# S4CX11.net
KiCad netlist of a schematic drawn in EAGLE
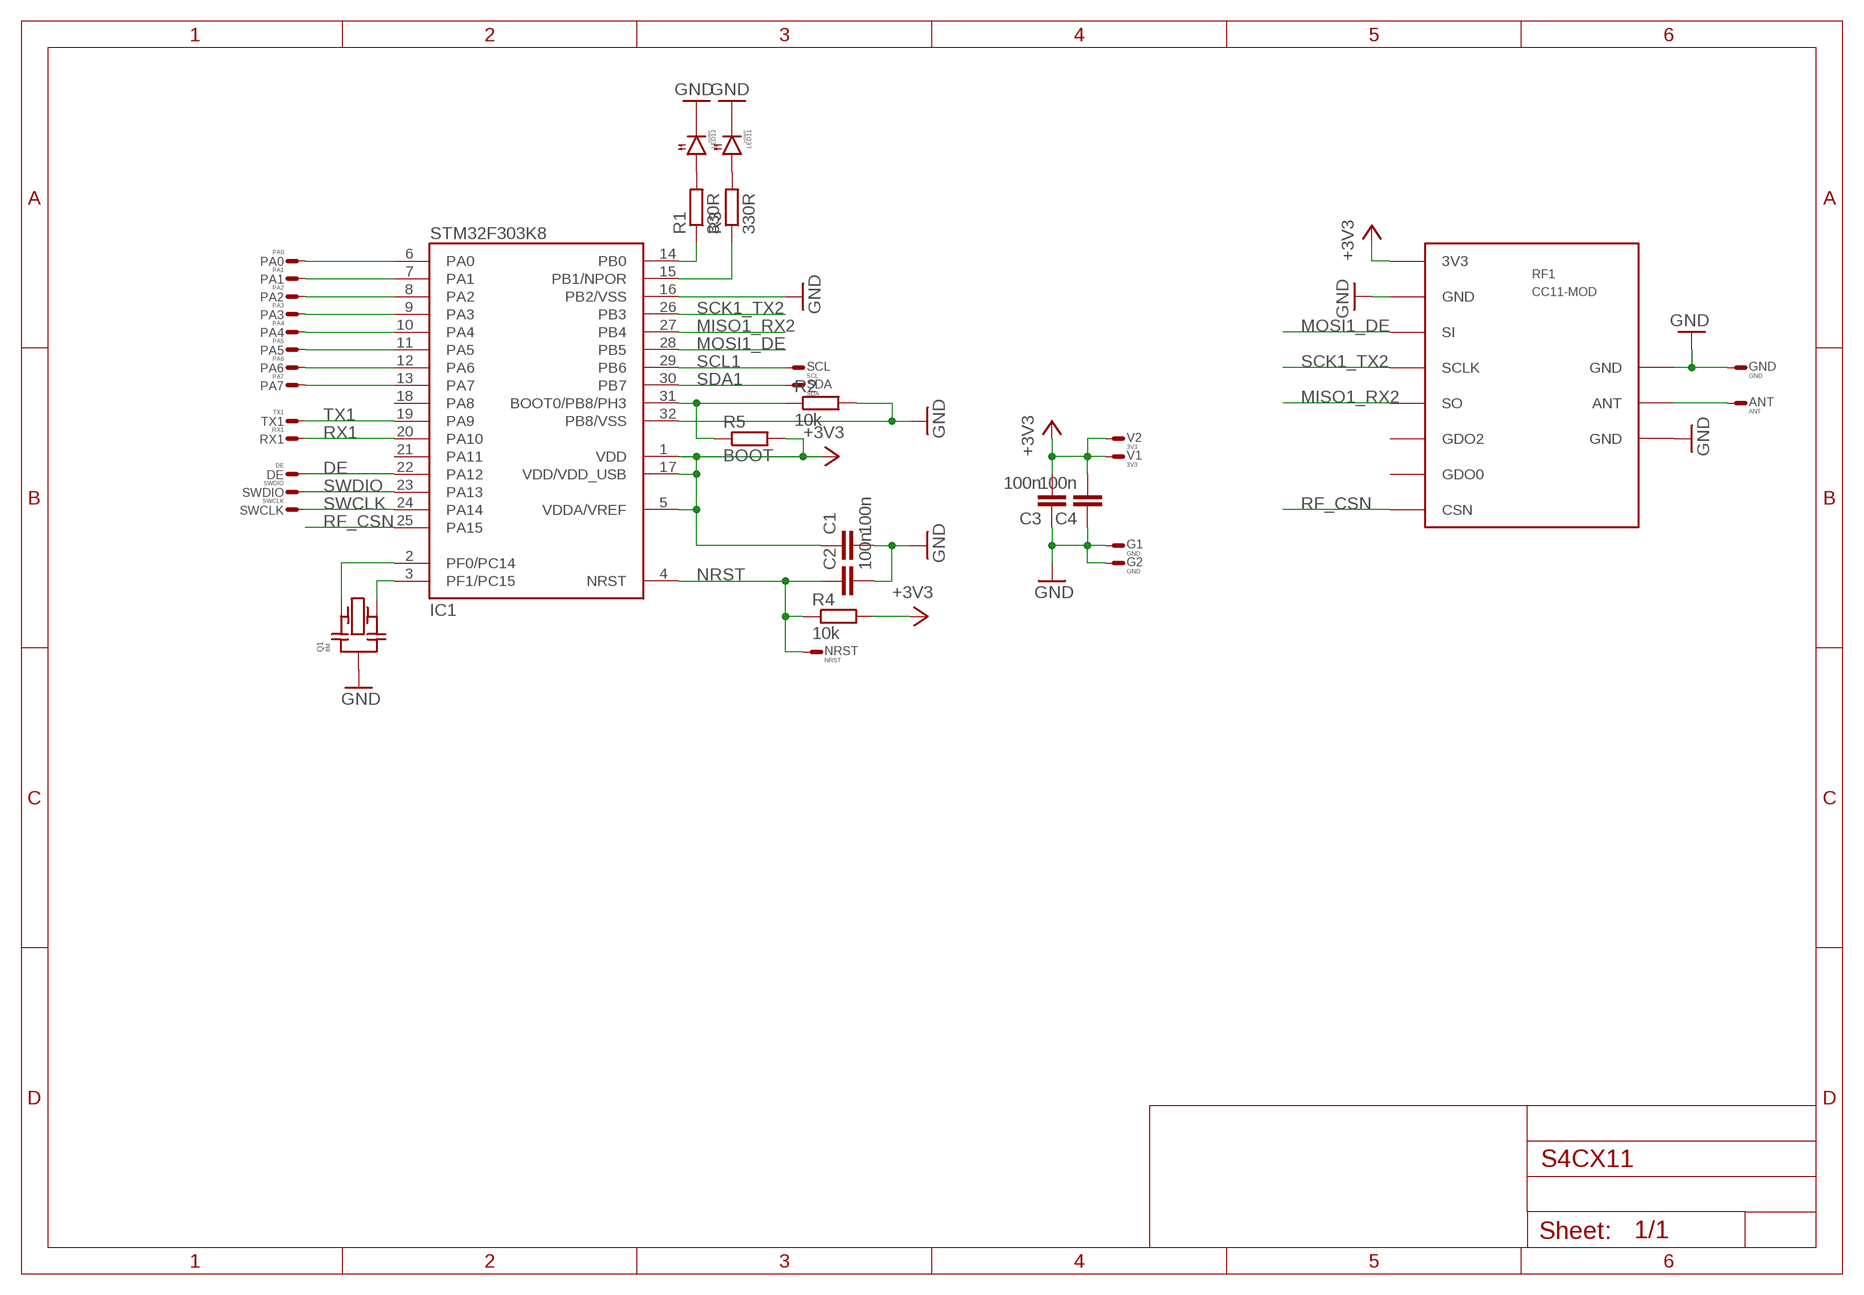
[diagram p0: schematic, sheet 1]

(export (version "E")
  (design (tool "Eeschema 10.0.6"))
  (components
    (comp (ref "ANT")
      (value "ANT")
      (footprint "eagle-import:T1.6_0.9")
      (libsource (lib "eagle-import") (part "WIREPADT1.6/0.9"))
    )
    (comp (ref "C1")
      (value "100n")
      (footprint "eagle-import:0603")
      (libsource (lib "eagle-import") (part "C0603"))
    )
    (comp (ref "C2")
      (value "100n")
      (footprint "eagle-import:0603")
      (libsource (lib "eagle-import") (part "C0603"))
    )
    (comp (ref "C3")
      (value "100n")
      (footprint "eagle-import:0603")
      (libsource (lib "eagle-import") (part "C0603"))
    )
    (comp (ref "C4")
      (value "100n")
      (footprint "eagle-import:0603")
      (libsource (lib "eagle-import") (part "C0603"))
    )
    (comp (ref "DE")
      (value "DE")
      (footprint "eagle-import:T1.6_0.9")
      (libsource (lib "eagle-import") (part "WIREPADT1.6/0.9"))
    )
    (comp (ref "G1")
      (value "GND")
      (footprint "eagle-import:T1.6_0.9")
      (libsource (lib "eagle-import") (part "WIREPADT1.6/0.9"))
    )
    (comp (ref "G2")
      (value "GND")
      (footprint "eagle-import:T1.6_0.9")
      (libsource (lib "eagle-import") (part "WIREPADT1.6/0.9"))
    )
    (comp (ref "GND")
      (value "GND")
      (footprint "eagle-import:T1.6_0.9")
      (libsource (lib "eagle-import") (part "WIREPADT1.6/0.9"))
    )
    (comp (ref "IC1")
      (value "STM32F303K8")
      (footprint "eagle-import:LQFP32-7X7")
      (libsource (lib "eagle-import") (part "STM32_LQFP32"))
    )
    (comp (ref "LED1")
      (value "HSMF")
      (footprint "eagle-import:HSMF")
      (libsource (lib "eagle-import") (part "2LEDH"))
    )
    (comp (ref "NRST")
      (value "NRST")
      (footprint "eagle-import:T1.6_0.9")
      (libsource (lib "eagle-import") (part "WIREPADT1.6/0.9"))
    )
    (comp (ref "PA0")
      (value "PA0")
      (footprint "eagle-import:T1.6_0.9")
      (libsource (lib "eagle-import") (part "WIREPADT1.6/0.9"))
    )
    (comp (ref "PA1")
      (value "PA1")
      (footprint "eagle-import:T1.6_0.9")
      (libsource (lib "eagle-import") (part "WIREPADT1.6/0.9"))
    )
    (comp (ref "PA2")
      (value "PA2")
      (footprint "eagle-import:T1.6_0.9")
      (libsource (lib "eagle-import") (part "WIREPADT1.6/0.9"))
    )
    (comp (ref "PA3")
      (value "PA3")
      (footprint "eagle-import:T1.6_0.9")
      (libsource (lib "eagle-import") (part "WIREPADT1.6/0.9"))
    )
    (comp (ref "PA4")
      (value "PA4")
      (footprint "eagle-import:T1.6_0.9")
      (libsource (lib "eagle-import") (part "WIREPADT1.6/0.9"))
    )
    (comp (ref "PA5")
      (value "PA5")
      (footprint "eagle-import:T1.6_0.9")
      (libsource (lib "eagle-import") (part "WIREPADT1.6/0.9"))
    )
    (comp (ref "PA6")
      (value "PA6")
      (footprint "eagle-import:T1.6_0.9")
      (libsource (lib "eagle-import") (part "WIREPADT1.6/0.9"))
    )
    (comp (ref "PA7")
      (value "PA7")
      (footprint "eagle-import:T1.6_0.9")
      (libsource (lib "eagle-import") (part "WIREPADT1.6/0.9"))
    )
    (comp (ref "Q1")
      (value "8M")
      (footprint "eagle-import:CSTCE")
      (libsource (lib "eagle-import") (part "QRCE"))
    )
    (comp (ref "R1")
      (value "330R")
      (footprint "eagle-import:0603")
      (libsource (lib "eagle-import") (part "R0603"))
    )
    (comp (ref "R2")
      (value "10k")
      (footprint "eagle-import:0603")
      (libsource (lib "eagle-import") (part "R0603"))
    )
    (comp (ref "R3")
      (value "330R")
      (footprint "eagle-import:0603")
      (libsource (lib "eagle-import") (part "R0603"))
    )
    (comp (ref "R4")
      (value "10k")
      (footprint "eagle-import:0603")
      (libsource (lib "eagle-import") (part "R0603"))
    )
    (comp (ref "R5")
      (value "BOOT")
      (footprint "eagle-import:1206")
      (libsource (lib "eagle-import") (part "R1206"))
    )
    (comp (ref "RF1")
      (value "CC11-MOD")
      (footprint "eagle-import:CC11-MOD")
      (libsource (lib "eagle-import") (part "CC11-MOD"))
    )
    (comp (ref "RX1")
      (value "RX1")
      (footprint "eagle-import:T1.6_0.9")
      (libsource (lib "eagle-import") (part "WIREPADT1.6/0.9"))
    )
    (comp (ref "SCL")
      (value "SCL")
      (footprint "eagle-import:T1.6_0.9")
      (libsource (lib "eagle-import") (part "WIREPADT1.6/0.9"))
    )
    (comp (ref "SDA")
      (value "SDA")
      (footprint "eagle-import:T1.6_0.9")
      (libsource (lib "eagle-import") (part "WIREPADT1.6/0.9"))
    )
    (comp (ref "SWCLK")
      (value "SWCLK")
      (footprint "eagle-import:T1.6_0.9")
      (libsource (lib "eagle-import") (part "WIREPADT1.6/0.9"))
    )
    (comp (ref "SWDIO")
      (value "SWDIO")
      (footprint "eagle-import:T1.6_0.9")
      (libsource (lib "eagle-import") (part "WIREPADT1.6/0.9"))
    )
    (comp (ref "TX1")
      (value "TX1")
      (footprint "eagle-import:T1.6_0.9")
      (libsource (lib "eagle-import") (part "WIREPADT1.6/0.9"))
    )
    (comp (ref "V1")
      (value "3V3")
      (footprint "eagle-import:T1.6_0.9")
      (libsource (lib "eagle-import") (part "WIREPADT1.6/0.9"))
    )
    (comp (ref "V2")
      (value "3V3")
      (footprint "eagle-import:T1.6_0.9")
      (libsource (lib "eagle-import") (part "WIREPADT1.6/0.9"))
    )
  )
  (nets
    (net (code "1") (name "+3V3") (class "Default")
      (node (ref "C1") (pin "1") (pinfunction "1_1") (pintype "passive"))
      (node (ref "C3") (pin "2") (pinfunction "2_2") (pintype "passive"))
      (node (ref "C4") (pin "2") (pinfunction "2_2") (pintype "passive"))
      (node (ref "IC1") (pin "1") (pinfunction "VDD_1") (pintype "bidirectional"))
      (node (ref "IC1") (pin "17") (pinfunction "VDD/VDD_USB_17") (pintype "bidirectional"))
      (node (ref "IC1") (pin "5") (pinfunction "VDDA/VREF_5") (pintype "bidirectional"))
      (node (ref "R4") (pin "2") (pinfunction "2_2") (pintype "passive"))
      (node (ref "R5") (pin "2") (pinfunction "2_2") (pintype "passive"))
      (node (ref "RF1") (pin "3V3") (pinfunction "3V3_3V3") (pintype "bidirectional"))
      (node (ref "V1") (pin "1") (pinfunction "S_1") (pintype "passive"))
      (node (ref "V2") (pin "1") (pinfunction "S_1") (pintype "passive"))
    )
    (net (code "2") (name "/DE") (class "Default")
      (node (ref "DE") (pin "1") (pinfunction "S_1") (pintype "passive"))
      (node (ref "IC1") (pin "22") (pinfunction "PA12_22") (pintype "bidirectional"))
    )
    (net (code "3") (name "/MISO1_RX2") (class "Default")
      (node (ref "IC1") (pin "27") (pinfunction "PB4_27") (pintype "bidirectional"))
      (node (ref "RF1") (pin "SO") (pinfunction "SO_SO") (pintype "bidirectional"))
    )
    (net (code "4") (name "/MOSI1_DE") (class "Default")
      (node (ref "IC1") (pin "28") (pinfunction "PB5_28") (pintype "bidirectional"))
      (node (ref "RF1") (pin "SI") (pinfunction "SI_SI") (pintype "bidirectional"))
    )
    (net (code "5") (name "/NRST") (class "Default")
      (node (ref "C2") (pin "1") (pinfunction "1_1") (pintype "passive"))
      (node (ref "IC1") (pin "4") (pinfunction "NRST_4") (pintype "bidirectional"))
      (node (ref "NRST") (pin "1") (pinfunction "S_1") (pintype "passive"))
      (node (ref "R4") (pin "1") (pinfunction "1_1") (pintype "passive"))
    )
    (net (code "6") (name "/RF_CSN") (class "Default")
      (node (ref "IC1") (pin "25") (pinfunction "PA15_25") (pintype "bidirectional"))
      (node (ref "RF1") (pin "CSN") (pinfunction "CSN_CSN") (pintype "bidirectional"))
    )
    (net (code "7") (name "/RX1") (class "Default")
      (node (ref "IC1") (pin "20") (pinfunction "PA10_20") (pintype "bidirectional"))
      (node (ref "RX1") (pin "1") (pinfunction "S_1") (pintype "passive"))
    )
    (net (code "8") (name "/SCK1_TX2") (class "Default")
      (node (ref "IC1") (pin "26") (pinfunction "PB3_26") (pintype "bidirectional"))
      (node (ref "RF1") (pin "SCLK") (pinfunction "SCLK_SCLK") (pintype "bidirectional"))
    )
    (net (code "9") (name "/SCL1") (class "Default")
      (node (ref "IC1") (pin "29") (pinfunction "PB6_29") (pintype "bidirectional"))
      (node (ref "SCL") (pin "1") (pinfunction "S_1") (pintype "passive"))
    )
    (net (code "10") (name "/SDA1") (class "Default")
      (node (ref "IC1") (pin "30") (pinfunction "PB7_30") (pintype "bidirectional"))
      (node (ref "SDA") (pin "1") (pinfunction "S_1") (pintype "passive"))
    )
    (net (code "11") (name "/SWCLK") (class "Default")
      (node (ref "IC1") (pin "24") (pinfunction "PA14_24") (pintype "bidirectional"))
      (node (ref "SWCLK") (pin "1") (pinfunction "S_1") (pintype "passive"))
    )
    (net (code "12") (name "/SWDIO") (class "Default")
      (node (ref "IC1") (pin "23") (pinfunction "PA13_23") (pintype "bidirectional"))
      (node (ref "SWDIO") (pin "1") (pinfunction "S_1") (pintype "passive"))
    )
    (net (code "13") (name "/TX1") (class "Default")
      (node (ref "IC1") (pin "19") (pinfunction "PA9_19") (pintype "bidirectional"))
      (node (ref "TX1") (pin "1") (pinfunction "S_1") (pintype "passive"))
    )
    (net (code "14") (name "GND") (class "Default")
      (node (ref "C1") (pin "2") (pinfunction "2_2") (pintype "passive"))
      (node (ref "C2") (pin "2") (pinfunction "2_2") (pintype "passive"))
      (node (ref "C3") (pin "1") (pinfunction "1_1") (pintype "passive"))
      (node (ref "C4") (pin "1") (pinfunction "1_1") (pintype "passive"))
      (node (ref "G1") (pin "1") (pinfunction "S_1") (pintype "passive"))
      (node (ref "G2") (pin "1") (pinfunction "S_1") (pintype "passive"))
      (node (ref "GND") (pin "1") (pinfunction "S_1") (pintype "passive"))
      (node (ref "IC1") (pin "16") (pinfunction "PB2/VSS_16") (pintype "bidirectional"))
      (node (ref "IC1") (pin "32") (pinfunction "PB8/VSS_32") (pintype "bidirectional"))
      (node (ref "LED1") (pin "2") (pinfunction "C_2") (pintype "bidirectional"))
      (node (ref "LED1") (pin "4") (pinfunction "C_4") (pintype "bidirectional"))
      (node (ref "Q1") (pin "G") (pinfunction "M_G") (pintype "passive"))
      (node (ref "R2") (pin "2") (pinfunction "2_2") (pintype "passive"))
      (node (ref "RF1") (pin "GND@1") (pinfunction "GND_GND@1") (pintype "bidirectional"))
      (node (ref "RF1") (pin "GND@2") (pinfunction "GND_GND@2") (pintype "bidirectional"))
      (node (ref "RF1") (pin "GND@3") (pinfunction "GND_GND@3") (pintype "bidirectional"))
    )
    (net (code "15") (name "Net-(ANT-S)") (class "Default")
      (node (ref "ANT") (pin "1") (pinfunction "S_1") (pintype "passive"))
      (node (ref "RF1") (pin "ANT") (pinfunction "ANT_ANT") (pintype "bidirectional"))
    )
    (net (code "16") (name "Net-(IC1-BOOT0{slash}PB8{slash}PH3)") (class "Default")
      (node (ref "IC1") (pin "31") (pinfunction "BOOT0/PB8/PH3_31") (pintype "bidirectional"))
      (node (ref "R2") (pin "1") (pinfunction "1_1") (pintype "passive"))
      (node (ref "R5") (pin "1") (pinfunction "1_1") (pintype "passive"))
    )
    (net (code "17") (name "Net-(IC1-PA0)") (class "Default")
      (node (ref "IC1") (pin "6") (pinfunction "PA0_6") (pintype "bidirectional"))
      (node (ref "PA0") (pin "1") (pinfunction "S_1") (pintype "passive"))
    )
    (net (code "18") (name "Net-(IC1-PA1)") (class "Default")
      (node (ref "IC1") (pin "7") (pinfunction "PA1_7") (pintype "bidirectional"))
      (node (ref "PA1") (pin "1") (pinfunction "S_1") (pintype "passive"))
    )
    (net (code "19") (name "Net-(IC1-PA2)") (class "Default")
      (node (ref "IC1") (pin "8") (pinfunction "PA2_8") (pintype "bidirectional"))
      (node (ref "PA2") (pin "1") (pinfunction "S_1") (pintype "passive"))
    )
    (net (code "20") (name "Net-(IC1-PA3)") (class "Default")
      (node (ref "IC1") (pin "9") (pinfunction "PA3_9") (pintype "bidirectional"))
      (node (ref "PA3") (pin "1") (pinfunction "S_1") (pintype "passive"))
    )
    (net (code "21") (name "Net-(IC1-PA4)") (class "Default")
      (node (ref "IC1") (pin "10") (pinfunction "PA4_10") (pintype "bidirectional"))
      (node (ref "PA4") (pin "1") (pinfunction "S_1") (pintype "passive"))
    )
    (net (code "22") (name "Net-(IC1-PA5)") (class "Default")
      (node (ref "IC1") (pin "11") (pinfunction "PA5_11") (pintype "bidirectional"))
      (node (ref "PA5") (pin "1") (pinfunction "S_1") (pintype "passive"))
    )
    (net (code "23") (name "Net-(IC1-PA6)") (class "Default")
      (node (ref "IC1") (pin "12") (pinfunction "PA6_12") (pintype "bidirectional"))
      (node (ref "PA6") (pin "1") (pinfunction "S_1") (pintype "passive"))
    )
    (net (code "24") (name "Net-(IC1-PA7)") (class "Default")
      (node (ref "IC1") (pin "13") (pinfunction "PA7_13") (pintype "bidirectional"))
      (node (ref "PA7") (pin "1") (pinfunction "S_1") (pintype "passive"))
    )
    (net (code "25") (name "Net-(IC1-PB0)") (class "Default")
      (node (ref "IC1") (pin "14") (pinfunction "PB0_14") (pintype "bidirectional"))
      (node (ref "R1") (pin "1") (pinfunction "1_1") (pintype "passive"))
    )
    (net (code "26") (name "Net-(IC1-PB1{slash}NPOR)") (class "Default")
      (node (ref "IC1") (pin "15") (pinfunction "PB1/NPOR_15") (pintype "bidirectional"))
      (node (ref "R3") (pin "1") (pinfunction "1_1") (pintype "passive"))
    )
    (net (code "27") (name "Net-(IC1-PF0{slash}PC14)") (class "Default")
      (node (ref "IC1") (pin "2") (pinfunction "PF0/PC14_2") (pintype "bidirectional"))
      (node (ref "Q1") (pin "A") (pinfunction "1_A") (pintype "passive"))
    )
    (net (code "28") (name "Net-(IC1-PF1{slash}PC15)") (class "Default")
      (node (ref "IC1") (pin "3") (pinfunction "PF1/PC15_3") (pintype "bidirectional"))
      (node (ref "Q1") (pin "B") (pinfunction "2_B") (pintype "passive"))
    )
    (net (code "29") (name "Net-(LED1A-A)") (class "Default")
      (node (ref "LED1") (pin "1") (pinfunction "A_1") (pintype "bidirectional"))
      (node (ref "R3") (pin "2") (pinfunction "2_2") (pintype "passive"))
    )
    (net (code "30") (name "Net-(LED1B-A)") (class "Default")
      (node (ref "LED1") (pin "3") (pinfunction "A_3") (pintype "bidirectional"))
      (node (ref "R1") (pin "2") (pinfunction "2_2") (pintype "passive"))
    )
    (net (code "31") (name "unconnected-(IC1-PA8-Pad18)") (class "Default")
      (node (ref "IC1") (pin "18") (pinfunction "PA8_18") (pintype "bidirectional"))
    )
    (net (code "32") (name "unconnected-(IC1-PA11-Pad21)") (class "Default")
      (node (ref "IC1") (pin "21") (pinfunction "PA11_21") (pintype "bidirectional"))
    )
    (net (code "33") (name "unconnected-(RF1-PadGDO0)") (class "Default")
      (node (ref "RF1") (pin "GDO0") (pinfunction "GDO0_GDO0") (pintype "bidirectional"))
    )
    (net (code "34") (name "unconnected-(RF1-PadGDO2)") (class "Default")
      (node (ref "RF1") (pin "GDO2") (pinfunction "GDO2_GDO2") (pintype "bidirectional"))
    )
  )
)
